# DDR3.net
KiCad netlist of a schematic drawn in Altium Designer
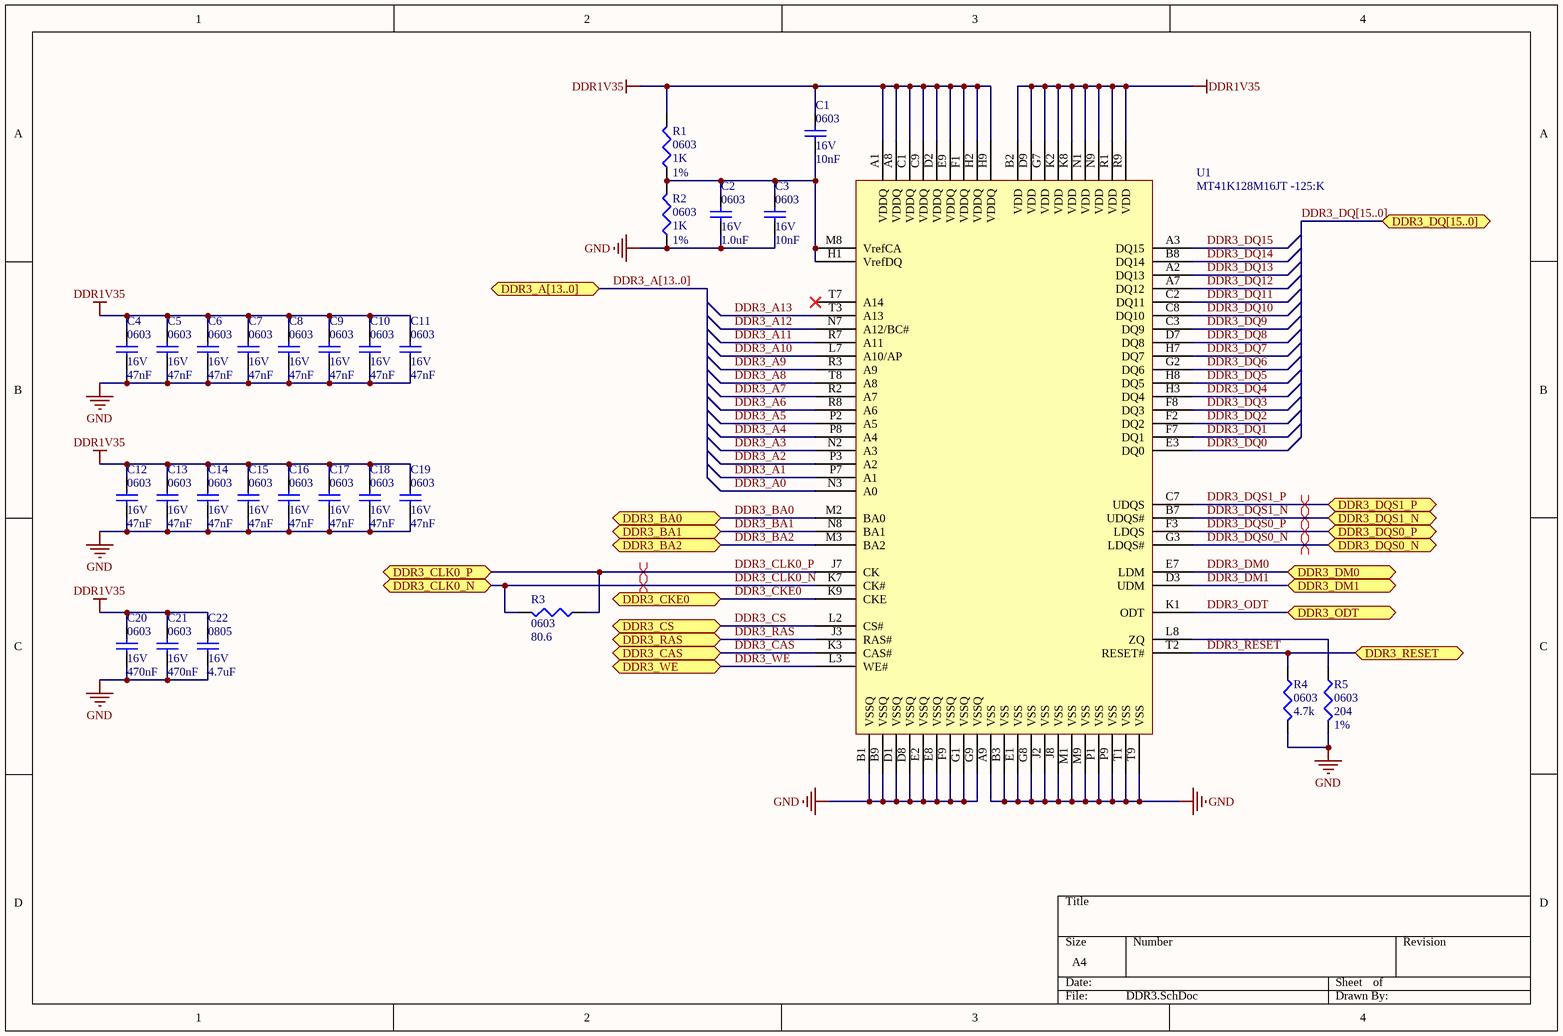
[diagram p0: DDR3.SchDoc]

(export (version "E")
  (design (tool "Eeschema 10.0.6"))
  (components
    (comp (ref "C1")
      (value "10nF")
      (footprint "1608[0603]")
      (description "Capacitor (Semiconductor SIM Model)")
      (fields
        (field (name "PACKAGEREFERENCE") "0603")
        (field (name "V") "16V")
        (field (name "PUBLISHER") "Altium Limited")
      )
      (libsource (lib "Devices") (part "Cap Semi"))
    )
    (comp (ref "C2")
      (value "1.0uF")
      (footprint "1608[0603]")
      (description "Capacitor (Semiconductor SIM Model)")
      (fields
        (field (name "PACKAGEREFERENCE") "0603")
        (field (name "V") "16V")
        (field (name "PUBLISHER") "Altium Limited")
      )
      (libsource (lib "Devices") (part "Cap Semi"))
    )
    (comp (ref "C3")
      (value "10nF")
      (footprint "1608[0603]")
      (description "Capacitor (Semiconductor SIM Model)")
      (fields
        (field (name "PACKAGEREFERENCE") "0603")
        (field (name "V") "16V")
        (field (name "PUBLISHER") "Altium Limited")
      )
      (libsource (lib "Devices") (part "Cap Semi"))
    )
    (comp (ref "C4")
      (value "47nF")
      (footprint "1608[0603]")
      (description "Capacitor (Semiconductor SIM Model)")
      (fields
        (field (name "PACKAGEREFERENCE") "0603")
        (field (name "V") "16V")
        (field (name "PUBLISHER") "Altium Limited")
      )
      (libsource (lib "Devices") (part "Cap Semi"))
    )
    (comp (ref "C5")
      (value "47nF")
      (footprint "1608[0603]")
      (description "Capacitor (Semiconductor SIM Model)")
      (fields
        (field (name "PACKAGEREFERENCE") "0603")
        (field (name "V") "16V")
        (field (name "PUBLISHER") "Altium Limited")
      )
      (libsource (lib "Devices") (part "Cap Semi"))
    )
    (comp (ref "C6")
      (value "47nF")
      (footprint "1608[0603]")
      (description "Capacitor (Semiconductor SIM Model)")
      (fields
        (field (name "PACKAGEREFERENCE") "0603")
        (field (name "V") "16V")
        (field (name "PUBLISHER") "Altium Limited")
      )
      (libsource (lib "Devices") (part "Cap Semi"))
    )
    (comp (ref "C7")
      (value "47nF")
      (footprint "1608[0603]")
      (description "Capacitor (Semiconductor SIM Model)")
      (fields
        (field (name "PACKAGEREFERENCE") "0603")
        (field (name "V") "16V")
        (field (name "PUBLISHER") "Altium Limited")
      )
      (libsource (lib "Devices") (part "Cap Semi"))
    )
    (comp (ref "C8")
      (value "47nF")
      (footprint "1608[0603]")
      (description "Capacitor (Semiconductor SIM Model)")
      (fields
        (field (name "PACKAGEREFERENCE") "0603")
        (field (name "V") "16V")
        (field (name "PUBLISHER") "Altium Limited")
      )
      (libsource (lib "Devices") (part "Cap Semi"))
    )
    (comp (ref "C9")
      (value "47nF")
      (footprint "1608[0603]")
      (description "Capacitor (Semiconductor SIM Model)")
      (fields
        (field (name "PACKAGEREFERENCE") "0603")
        (field (name "V") "16V")
        (field (name "PUBLISHER") "Altium Limited")
      )
      (libsource (lib "Devices") (part "Cap Semi"))
    )
    (comp (ref "C10")
      (value "47nF")
      (footprint "1608[0603]")
      (description "Capacitor (Semiconductor SIM Model)")
      (fields
        (field (name "PACKAGEREFERENCE") "0603")
        (field (name "V") "16V")
        (field (name "PUBLISHER") "Altium Limited")
      )
      (libsource (lib "Devices") (part "Cap Semi"))
    )
    (comp (ref "C11")
      (value "47nF")
      (footprint "1608[0603]")
      (description "Capacitor (Semiconductor SIM Model)")
      (fields
        (field (name "PACKAGEREFERENCE") "0603")
        (field (name "V") "16V")
        (field (name "PUBLISHER") "Altium Limited")
      )
      (libsource (lib "Devices") (part "Cap Semi"))
    )
    (comp (ref "C12")
      (value "47nF")
      (footprint "1608[0603]")
      (description "Capacitor (Semiconductor SIM Model)")
      (fields
        (field (name "PACKAGEREFERENCE") "0603")
        (field (name "V") "16V")
        (field (name "PUBLISHER") "Altium Limited")
      )
      (libsource (lib "Devices") (part "Cap Semi"))
    )
    (comp (ref "C13")
      (value "47nF")
      (footprint "1608[0603]")
      (description "Capacitor (Semiconductor SIM Model)")
      (fields
        (field (name "PACKAGEREFERENCE") "0603")
        (field (name "V") "16V")
        (field (name "PUBLISHER") "Altium Limited")
      )
      (libsource (lib "Devices") (part "Cap Semi"))
    )
    (comp (ref "C14")
      (value "47nF")
      (footprint "1608[0603]")
      (description "Capacitor (Semiconductor SIM Model)")
      (fields
        (field (name "PACKAGEREFERENCE") "0603")
        (field (name "V") "16V")
        (field (name "PUBLISHER") "Altium Limited")
      )
      (libsource (lib "Devices") (part "Cap Semi"))
    )
    (comp (ref "C15")
      (value "47nF")
      (footprint "1608[0603]")
      (description "Capacitor (Semiconductor SIM Model)")
      (fields
        (field (name "PACKAGEREFERENCE") "0603")
        (field (name "V") "16V")
        (field (name "PUBLISHER") "Altium Limited")
      )
      (libsource (lib "Devices") (part "Cap Semi"))
    )
    (comp (ref "C16")
      (value "47nF")
      (footprint "1608[0603]")
      (description "Capacitor (Semiconductor SIM Model)")
      (fields
        (field (name "PACKAGEREFERENCE") "0603")
        (field (name "V") "16V")
        (field (name "PUBLISHER") "Altium Limited")
      )
      (libsource (lib "Devices") (part "Cap Semi"))
    )
    (comp (ref "C17")
      (value "47nF")
      (footprint "1608[0603]")
      (description "Capacitor (Semiconductor SIM Model)")
      (fields
        (field (name "PACKAGEREFERENCE") "0603")
        (field (name "V") "16V")
        (field (name "PUBLISHER") "Altium Limited")
      )
      (libsource (lib "Devices") (part "Cap Semi"))
    )
    (comp (ref "C18")
      (value "47nF")
      (footprint "1608[0603]")
      (description "Capacitor (Semiconductor SIM Model)")
      (fields
        (field (name "PACKAGEREFERENCE") "0603")
        (field (name "V") "16V")
        (field (name "PUBLISHER") "Altium Limited")
      )
      (libsource (lib "Devices") (part "Cap Semi"))
    )
    (comp (ref "C19")
      (value "47nF")
      (footprint "1608[0603]")
      (description "Capacitor (Semiconductor SIM Model)")
      (fields
        (field (name "PACKAGEREFERENCE") "0603")
        (field (name "V") "16V")
        (field (name "PUBLISHER") "Altium Limited")
      )
      (libsource (lib "Devices") (part "Cap Semi"))
    )
    (comp (ref "C20")
      (value "470nF")
      (footprint "1608[0603]")
      (description "Capacitor (Semiconductor SIM Model)")
      (fields
        (field (name "PACKAGEREFERENCE") "0603")
        (field (name "V") "16V")
        (field (name "PUBLISHER") "Altium Limited")
      )
      (libsource (lib "Devices") (part "Cap Semi"))
    )
    (comp (ref "C21")
      (value "470nF")
      (footprint "1608[0603]")
      (description "Capacitor (Semiconductor SIM Model)")
      (fields
        (field (name "PACKAGEREFERENCE") "0603")
        (field (name "V") "16V")
        (field (name "PUBLISHER") "Altium Limited")
      )
      (libsource (lib "Devices") (part "Cap Semi"))
    )
    (comp (ref "C22")
      (value "4.7uF")
      (footprint "2012[0805]")
      (description "Capacitor (Semiconductor SIM Model)")
      (fields
        (field (name "PACKAGEREFERENCE") "0805")
        (field (name "V") "16V")
        (field (name "PUBLISHER") "Altium Limited")
      )
      (libsource (lib "Devices") (part "Cap Semi"))
    )
    (comp (ref "R1")
      (value "1K")
      (footprint "1608[0603]")
      (description "Resistor")
      (fields
        (field (name "PACKAGEREFERENCE") "0603")
        (field (name "ACCURACY") "1%")
        (field (name "Comment") "Res3")
        (field (name "PUBLISHER") "Altium Limited")
      )
      (libsource (lib "Miscellaneous Devices") (part "Res3"))
    )
    (comp (ref "R2")
      (value "1K")
      (footprint "1608[0603]")
      (description "Resistor")
      (fields
        (field (name "PACKAGEREFERENCE") "0603")
        (field (name "ACCURACY") "1%")
        (field (name "Comment") "Res3")
        (field (name "PUBLISHER") "Altium Limited")
      )
      (libsource (lib "Miscellaneous Devices") (part "Res3"))
    )
    (comp (ref "R3")
      (value "80.6")
      (footprint "1608[0603]")
      (description "Resistor")
      (fields
        (field (name "PACKAGEREFERENCE") "0603")
        (field (name "Comment") "Res3")
        (field (name "PUBLISHER") "Altium Limited")
      )
      (libsource (lib "Miscellaneous Devices") (part "Res3"))
    )
    (comp (ref "R4")
      (value "4.7k")
      (footprint "1608[0603]")
      (description "Resistor")
      (fields
        (field (name "PACKAGEREFERENCE") "0603")
        (field (name "Comment") "Res3")
        (field (name "PUBLISHER") "Altium Limited")
      )
      (libsource (lib "Miscellaneous Devices") (part "Res3"))
    )
    (comp (ref "R5")
      (value "204")
      (footprint "1608[0603]")
      (description "Resistor")
      (fields
        (field (name "PACKAGEREFERENCE") "0603")
        (field (name "ACCURACY") "1%")
        (field (name "Comment") "Res3")
        (field (name "PUBLISHER") "Altium Limited")
      )
      (libsource (lib "Miscellaneous Devices") (part "Res3"))
    )
    (comp (ref "U1")
      (value "MT41K128M16JT -125:K")
      (footprint "MT41K128M16JT")
      (description "DDR3L")
      (libsource (lib "Spartan6_LX9_A0") (part "MT41K128M16JT -125{colon}K"))
    )
  )
  (nets
    (net (code "1") (name "/DDR3_A0") (class "Default")
      (node (ref "U1") (pin "N3") (pinfunction "A0_N3") (pintype "passive"))
    )
    (net (code "2") (name "/DDR3_A1") (class "Default")
      (node (ref "U1") (pin "P7") (pinfunction "A1_P7") (pintype "passive"))
    )
    (net (code "3") (name "/DDR3_A2") (class "Default")
      (node (ref "U1") (pin "P3") (pinfunction "A2_P3") (pintype "passive"))
    )
    (net (code "4") (name "/DDR3_A3") (class "Default")
      (node (ref "U1") (pin "N2") (pinfunction "A3_N2") (pintype "passive"))
    )
    (net (code "5") (name "/DDR3_A4") (class "Default")
      (node (ref "U1") (pin "P8") (pinfunction "A4_P8") (pintype "passive"))
    )
    (net (code "6") (name "/DDR3_A5") (class "Default")
      (node (ref "U1") (pin "P2") (pinfunction "A5_P2") (pintype "passive"))
    )
    (net (code "7") (name "/DDR3_A6") (class "Default")
      (node (ref "U1") (pin "R8") (pinfunction "A6_R8") (pintype "passive"))
    )
    (net (code "8") (name "/DDR3_A7") (class "Default")
      (node (ref "U1") (pin "R2") (pinfunction "A7_R2") (pintype "passive"))
    )
    (net (code "9") (name "/DDR3_A8") (class "Default")
      (node (ref "U1") (pin "T8") (pinfunction "A8_T8") (pintype "passive"))
    )
    (net (code "10") (name "/DDR3_A9") (class "Default")
      (node (ref "U1") (pin "R3") (pinfunction "A9_R3") (pintype "passive"))
    )
    (net (code "11") (name "/DDR3_A10") (class "Default")
      (node (ref "U1") (pin "L7") (pinfunction "A10/AP_L7") (pintype "passive"))
    )
    (net (code "12") (name "/DDR3_A11") (class "Default")
      (node (ref "U1") (pin "R7") (pinfunction "A11_R7") (pintype "passive"))
    )
    (net (code "13") (name "/DDR3_A12") (class "Default")
      (node (ref "U1") (pin "N7") (pinfunction "A12/BC#_N7") (pintype "passive"))
    )
    (net (code "14") (name "/DDR3_A13") (class "Default")
      (node (ref "U1") (pin "T3") (pinfunction "A13_T3") (pintype "passive"))
    )
    (net (code "16") (name "/DDR3_BA0") (class "Default")
      (node (ref "U1") (pin "M2") (pinfunction "BA0_M2") (pintype "passive"))
    )
    (net (code "17") (name "/DDR3_BA1") (class "Default")
      (node (ref "U1") (pin "N8") (pinfunction "BA1_N8") (pintype "passive"))
    )
    (net (code "18") (name "/DDR3_BA2") (class "Default")
      (node (ref "U1") (pin "M3") (pinfunction "BA2_M3") (pintype "passive"))
    )
    (net (code "19") (name "/DDR3_CAS") (class "Default")
      (node (ref "U1") (pin "K3") (pinfunction "CAS#_K3") (pintype "passive"))
    )
    (net (code "20") (name "/DDR3_CKE0") (class "Default")
      (node (ref "U1") (pin "K9") (pinfunction "CKE_K9") (pintype "passive"))
    )
    (net (code "21") (name "/DDR3_CLK0_N") (class "Default")
      (node (ref "R3") (pin "2") (pinfunction "2_2") (pintype "passive"))
      (node (ref "U1") (pin "K7") (pinfunction "CK#_K7") (pintype "passive"))
    )
    (net (code "22") (name "/DDR3_CLK0_P") (class "Default")
      (node (ref "R3") (pin "1") (pinfunction "1_1") (pintype "passive"))
      (node (ref "U1") (pin "J7") (pinfunction "CK_J7") (pintype "passive"))
    )
    (net (code "23") (name "/DDR3_CS") (class "Default")
      (node (ref "U1") (pin "L2") (pinfunction "CS#_L2") (pintype "passive"))
    )
    (net (code "24") (name "/DDR3_DM0") (class "Default")
      (node (ref "U1") (pin "E7") (pinfunction "LDM_E7") (pintype "passive"))
    )
    (net (code "25") (name "/DDR3_DM1") (class "Default")
      (node (ref "U1") (pin "D3") (pinfunction "UDM_D3") (pintype "passive"))
    )
    (net (code "26") (name "/DDR3_DQ0") (class "Default")
      (node (ref "U1") (pin "E3") (pinfunction "DQ0_E3") (pintype "passive"))
    )
    (net (code "27") (name "/DDR3_DQ1") (class "Default")
      (node (ref "U1") (pin "F7") (pinfunction "DQ1_F7") (pintype "passive"))
    )
    (net (code "28") (name "/DDR3_DQ2") (class "Default")
      (node (ref "U1") (pin "F2") (pinfunction "DQ2_F2") (pintype "passive"))
    )
    (net (code "29") (name "/DDR3_DQ3") (class "Default")
      (node (ref "U1") (pin "F8") (pinfunction "DQ3_F8") (pintype "passive"))
    )
    (net (code "30") (name "/DDR3_DQ4") (class "Default")
      (node (ref "U1") (pin "H3") (pinfunction "DQ4_H3") (pintype "passive"))
    )
    (net (code "31") (name "/DDR3_DQ5") (class "Default")
      (node (ref "U1") (pin "H8") (pinfunction "DQ5_H8") (pintype "passive"))
    )
    (net (code "32") (name "/DDR3_DQ6") (class "Default")
      (node (ref "U1") (pin "G2") (pinfunction "DQ6_G2") (pintype "passive"))
    )
    (net (code "33") (name "/DDR3_DQ7") (class "Default")
      (node (ref "U1") (pin "H7") (pinfunction "DQ7_H7") (pintype "passive"))
    )
    (net (code "34") (name "/DDR3_DQ8") (class "Default")
      (node (ref "U1") (pin "D7") (pinfunction "DQ8_D7") (pintype "passive"))
    )
    (net (code "35") (name "/DDR3_DQ9") (class "Default")
      (node (ref "U1") (pin "C3") (pinfunction "DQ9_C3") (pintype "passive"))
    )
    (net (code "36") (name "/DDR3_DQ10") (class "Default")
      (node (ref "U1") (pin "C8") (pinfunction "DQ10_C8") (pintype "passive"))
    )
    (net (code "37") (name "/DDR3_DQ11") (class "Default")
      (node (ref "U1") (pin "C2") (pinfunction "DQ11_C2") (pintype "passive"))
    )
    (net (code "38") (name "/DDR3_DQ12") (class "Default")
      (node (ref "U1") (pin "A7") (pinfunction "DQ12_A7") (pintype "passive"))
    )
    (net (code "39") (name "/DDR3_DQ13") (class "Default")
      (node (ref "U1") (pin "A2") (pinfunction "DQ13_A2") (pintype "passive"))
    )
    (net (code "40") (name "/DDR3_DQ14") (class "Default")
      (node (ref "U1") (pin "B8") (pinfunction "DQ14_B8") (pintype "passive"))
    )
    (net (code "41") (name "/DDR3_DQ15") (class "Default")
      (node (ref "U1") (pin "A3") (pinfunction "DQ15_A3") (pintype "passive"))
    )
    (net (code "42") (name "/DDR3_DQS0_N") (class "Default")
      (node (ref "U1") (pin "G3") (pinfunction "LDQS#_G3") (pintype "passive"))
    )
    (net (code "43") (name "/DDR3_DQS0_P") (class "Default")
      (node (ref "U1") (pin "F3") (pinfunction "LDQS_F3") (pintype "passive"))
    )
    (net (code "44") (name "/DDR3_DQS1_N") (class "Default")
      (node (ref "U1") (pin "B7") (pinfunction "UDQS#_B7") (pintype "passive"))
    )
    (net (code "45") (name "/DDR3_DQS1_P") (class "Default")
      (node (ref "U1") (pin "C7") (pinfunction "UDQS_C7") (pintype "passive"))
    )
    (net (code "47") (name "/DDR3_ODT") (class "Default")
      (node (ref "U1") (pin "K1") (pinfunction "ODT_K1") (pintype "passive"))
    )
    (net (code "48") (name "/DDR3_RAS") (class "Default")
      (node (ref "U1") (pin "J3") (pinfunction "RAS#_J3") (pintype "passive"))
    )
    (net (code "49") (name "/DDR3_RESET") (class "Default")
      (node (ref "R4") (pin "1") (pinfunction "1_1") (pintype "passive"))
      (node (ref "U1") (pin "T2") (pinfunction "RESET#_T2") (pintype "passive"))
    )
    (net (code "50") (name "/DDR3_WE") (class "Default")
      (node (ref "U1") (pin "L3") (pinfunction "WE#_L3") (pintype "passive"))
    )
    (net (code "51") (name "DDR1V35") (class "Default")
      (node (ref "C1") (pin "1") (pinfunction "1_1") (pintype "passive"))
      (node (ref "C10") (pin "1") (pinfunction "1_1") (pintype "passive"))
      (node (ref "C11") (pin "1") (pinfunction "1_1") (pintype "passive"))
      (node (ref "C12") (pin "1") (pinfunction "1_1") (pintype "passive"))
      (node (ref "C13") (pin "1") (pinfunction "1_1") (pintype "passive"))
      (node (ref "C14") (pin "1") (pinfunction "1_1") (pintype "passive"))
      (node (ref "C15") (pin "1") (pinfunction "1_1") (pintype "passive"))
      (node (ref "C16") (pin "1") (pinfunction "1_1") (pintype "passive"))
      (node (ref "C17") (pin "1") (pinfunction "1_1") (pintype "passive"))
      (node (ref "C18") (pin "1") (pinfunction "1_1") (pintype "passive"))
      (node (ref "C19") (pin "1") (pinfunction "1_1") (pintype "passive"))
      (node (ref "C20") (pin "1") (pinfunction "1_1") (pintype "passive"))
      (node (ref "C21") (pin "1") (pinfunction "1_1") (pintype "passive"))
      (node (ref "C22") (pin "1") (pinfunction "1_1") (pintype "passive"))
      (node (ref "C4") (pin "1") (pinfunction "1_1") (pintype "passive"))
      (node (ref "C5") (pin "1") (pinfunction "1_1") (pintype "passive"))
      (node (ref "C6") (pin "1") (pinfunction "1_1") (pintype "passive"))
      (node (ref "C7") (pin "1") (pinfunction "1_1") (pintype "passive"))
      (node (ref "C8") (pin "1") (pinfunction "1_1") (pintype "passive"))
      (node (ref "C9") (pin "1") (pinfunction "1_1") (pintype "passive"))
      (node (ref "R1") (pin "2") (pinfunction "2_2") (pintype "passive"))
      (node (ref "U1") (pin "A1") (pinfunction "VDDQ_A1") (pintype "passive"))
      (node (ref "U1") (pin "A8") (pinfunction "VDDQ_A8") (pintype "passive"))
      (node (ref "U1") (pin "B2") (pinfunction "VDD_B2") (pintype "passive"))
      (node (ref "U1") (pin "C1") (pinfunction "VDDQ_C1") (pintype "passive"))
      (node (ref "U1") (pin "C9") (pinfunction "VDDQ_C9") (pintype "passive"))
      (node (ref "U1") (pin "D2") (pinfunction "VDDQ_D2") (pintype "passive"))
      (node (ref "U1") (pin "D9") (pinfunction "VDD_D9") (pintype "passive"))
      (node (ref "U1") (pin "E9") (pinfunction "VDDQ_E9") (pintype "passive"))
      (node (ref "U1") (pin "F1") (pinfunction "VDDQ_F1") (pintype "passive"))
      (node (ref "U1") (pin "G7") (pinfunction "VDD_G7") (pintype "passive"))
      (node (ref "U1") (pin "H2") (pinfunction "VDDQ_H2") (pintype "passive"))
      (node (ref "U1") (pin "H9") (pinfunction "VDDQ_H9") (pintype "passive"))
      (node (ref "U1") (pin "K2") (pinfunction "VDD_K2") (pintype "passive"))
      (node (ref "U1") (pin "K8") (pinfunction "VDD_K8") (pintype "passive"))
      (node (ref "U1") (pin "N1") (pinfunction "VDD_N1") (pintype "passive"))
      (node (ref "U1") (pin "N9") (pinfunction "VDD_N9") (pintype "passive"))
      (node (ref "U1") (pin "R1") (pinfunction "VDD_R1") (pintype "passive"))
      (node (ref "U1") (pin "R9") (pinfunction "VDD_R9") (pintype "passive"))
    )
    (net (code "52") (name "GND") (class "Default")
      (node (ref "C10") (pin "2") (pinfunction "2_2") (pintype "passive"))
      (node (ref "C11") (pin "2") (pinfunction "2_2") (pintype "passive"))
      (node (ref "C12") (pin "2") (pinfunction "2_2") (pintype "passive"))
      (node (ref "C13") (pin "2") (pinfunction "2_2") (pintype "passive"))
      (node (ref "C14") (pin "2") (pinfunction "2_2") (pintype "passive"))
      (node (ref "C15") (pin "2") (pinfunction "2_2") (pintype "passive"))
      (node (ref "C16") (pin "2") (pinfunction "2_2") (pintype "passive"))
      (node (ref "C17") (pin "2") (pinfunction "2_2") (pintype "passive"))
      (node (ref "C18") (pin "2") (pinfunction "2_2") (pintype "passive"))
      (node (ref "C19") (pin "2") (pinfunction "2_2") (pintype "passive"))
      (node (ref "C2") (pin "2") (pinfunction "2_2") (pintype "passive"))
      (node (ref "C20") (pin "2") (pinfunction "2_2") (pintype "passive"))
      (node (ref "C21") (pin "2") (pinfunction "2_2") (pintype "passive"))
      (node (ref "C22") (pin "2") (pinfunction "2_2") (pintype "passive"))
      (node (ref "C3") (pin "2") (pinfunction "2_2") (pintype "passive"))
      (node (ref "C4") (pin "2") (pinfunction "2_2") (pintype "passive"))
      (node (ref "C5") (pin "2") (pinfunction "2_2") (pintype "passive"))
      (node (ref "C6") (pin "2") (pinfunction "2_2") (pintype "passive"))
      (node (ref "C7") (pin "2") (pinfunction "2_2") (pintype "passive"))
      (node (ref "C8") (pin "2") (pinfunction "2_2") (pintype "passive"))
      (node (ref "C9") (pin "2") (pinfunction "2_2") (pintype "passive"))
      (node (ref "R2") (pin "1") (pinfunction "1_1") (pintype "passive"))
      (node (ref "R4") (pin "2") (pinfunction "2_2") (pintype "passive"))
      (node (ref "R5") (pin "2") (pinfunction "2_2") (pintype "passive"))
      (node (ref "U1") (pin "A9") (pinfunction "VSS_A9") (pintype "passive"))
      (node (ref "U1") (pin "B1") (pinfunction "VSSQ_B1") (pintype "passive"))
      (node (ref "U1") (pin "B3") (pinfunction "VSS_B3") (pintype "passive"))
      (node (ref "U1") (pin "B9") (pinfunction "VSSQ_B9") (pintype "passive"))
      (node (ref "U1") (pin "D1") (pinfunction "VSSQ_D1") (pintype "passive"))
      (node (ref "U1") (pin "D8") (pinfunction "VSSQ_D8") (pintype "passive"))
      (node (ref "U1") (pin "E1") (pinfunction "VSS_E1") (pintype "passive"))
      (node (ref "U1") (pin "E2") (pinfunction "VSSQ_E2") (pintype "passive"))
      (node (ref "U1") (pin "E8") (pinfunction "VSSQ_E8") (pintype "passive"))
      (node (ref "U1") (pin "F9") (pinfunction "VSSQ_F9") (pintype "passive"))
      (node (ref "U1") (pin "G1") (pinfunction "VSSQ_G1") (pintype "passive"))
      (node (ref "U1") (pin "G8") (pinfunction "VSS_G8") (pintype "passive"))
      (node (ref "U1") (pin "G9") (pinfunction "VSSQ_G9") (pintype "passive"))
      (node (ref "U1") (pin "J2") (pinfunction "VSS_J2") (pintype "passive"))
      (node (ref "U1") (pin "J8") (pinfunction "VSS_J8") (pintype "passive"))
      (node (ref "U1") (pin "M1") (pinfunction "VSS_M1") (pintype "passive"))
      (node (ref "U1") (pin "M9") (pinfunction "VSS_M9") (pintype "passive"))
      (node (ref "U1") (pin "P1") (pinfunction "VSS_P1") (pintype "passive"))
      (node (ref "U1") (pin "P9") (pinfunction "VSS_P9") (pintype "passive"))
      (node (ref "U1") (pin "T1") (pinfunction "VSS_T1") (pintype "passive"))
      (node (ref "U1") (pin "T9") (pinfunction "VSS_T9") (pintype "passive"))
    )
    (net (code "53") (name "Net-(U1-VrefCA)") (class "Default")
      (node (ref "C1") (pin "2") (pinfunction "2_2") (pintype "passive"))
      (node (ref "C2") (pin "1") (pinfunction "1_1") (pintype "passive"))
      (node (ref "C3") (pin "1") (pinfunction "1_1") (pintype "passive"))
      (node (ref "R1") (pin "1") (pinfunction "1_1") (pintype "passive"))
      (node (ref "R2") (pin "2") (pinfunction "2_2") (pintype "passive"))
      (node (ref "U1") (pin "H1") (pinfunction "VrefDQ_H1") (pintype "passive"))
      (node (ref "U1") (pin "M8") (pinfunction "VrefCA_M8") (pintype "passive"))
    )
    (net (code "54") (name "Net-(U1-ZQ)") (class "Default")
      (node (ref "R5") (pin "1") (pinfunction "1_1") (pintype "passive"))
      (node (ref "U1") (pin "L8") (pinfunction "ZQ_L8") (pintype "passive"))
    )
    (net (code "55") (name "unconnected-(U1-A14-PadT7)") (class "Default")
      (node (ref "U1") (pin "T7") (pinfunction "A14_T7") (pintype "passive+no_connect"))
    )
  )
)
